# m2.net
KiCad netlist of a schematic drawn in EAGLE
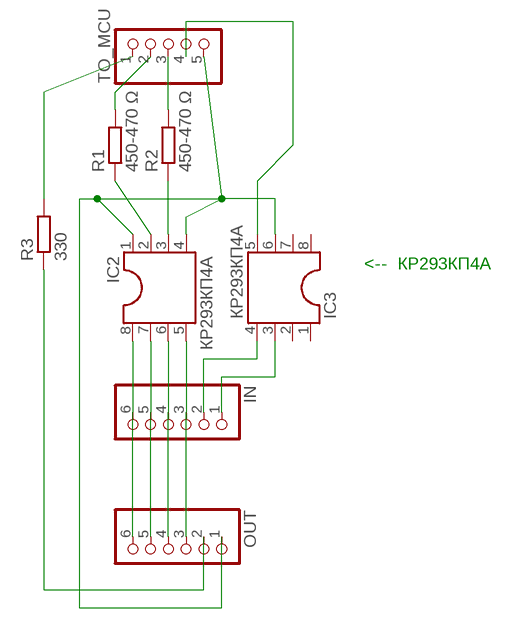
[diagram p0: schematic, sheet 1]

(export (version "E")
  (design (tool "Eeschema 10.0.6"))
  (components
    (comp (ref "IC2")
      (value "КР293КП4А")
      (footprint "eagle-import:DIL08")
      (libsource (lib "eagle-import") (part "DIL8"))
    )
    (comp (ref "IC3")
      (value "КР293КП4А")
      (footprint "eagle-import:DIL08")
      (libsource (lib "eagle-import") (part "DIL8"))
    )
    (comp (ref "IN")
      (value "PINHD-1X6")
      (footprint "eagle-import:1X06")
      (libsource (lib "eagle-import") (part "PINHD-1X6"))
    )
    (comp (ref "OUT")
      (value "PINHD-1X6")
      (footprint "eagle-import:1X06")
      (libsource (lib "eagle-import") (part "PINHD-1X6"))
    )
    (comp (ref "R1")
      (value "450-470 Ω")
      (footprint "eagle-import:0204_5")
      (libsource (lib "eagle-import") (part "R-EU_0204/5"))
    )
    (comp (ref "R2")
      (value "450-470 Ω")
      (footprint "eagle-import:0204_5")
      (libsource (lib "eagle-import") (part "R-EU_0204/5"))
    )
    (comp (ref "R3")
      (value "330")
      (footprint "eagle-import:0204_5")
      (libsource (lib "eagle-import") (part "R-EU_0204/5"))
    )
    (comp (ref "TO_MCU")
      (value "PINHD-1X5")
      (footprint "eagle-import:1X05")
      (libsource (lib "eagle-import") (part "PINHD-1X5"))
    )
  )
  (nets
    (net (code "1") (name "Net-(IC2-Pad1)") (class "Default")
      (node (ref "IC2") (pin "1") (pinfunction "1_1") (pintype "passive"))
      (node (ref "IC2") (pin "4") (pinfunction "4_4") (pintype "passive"))
      (node (ref "IC3") (pin "6") (pinfunction "6_6") (pintype "passive"))
      (node (ref "OUT") (pin "1") (pinfunction "1_1") (pintype "passive"))
      (node (ref "TO_MCU") (pin "5") (pinfunction "5_5") (pintype "passive"))
    )
    (net (code "2") (name "Net-(IC2-Pad2)") (class "Default")
      (node (ref "IC2") (pin "2") (pinfunction "2_2") (pintype "passive"))
      (node (ref "R1") (pin "1") (pinfunction "1_1") (pintype "passive"))
    )
    (net (code "3") (name "Net-(IC2-Pad3)") (class "Default")
      (node (ref "IC2") (pin "3") (pinfunction "3_3") (pintype "passive"))
      (node (ref "R2") (pin "1") (pinfunction "1_1") (pintype "passive"))
    )
    (net (code "4") (name "Net-(IC2-Pad5)") (class "Default")
      (node (ref "IC2") (pin "5") (pinfunction "5_5") (pintype "passive"))
      (node (ref "IN") (pin "3") (pinfunction "3_3") (pintype "passive"))
      (node (ref "OUT") (pin "3") (pinfunction "3_3") (pintype "passive"))
    )
    (net (code "5") (name "Net-(IC2-Pad6)") (class "Default")
      (node (ref "IC2") (pin "6") (pinfunction "6_6") (pintype "passive"))
      (node (ref "IN") (pin "4") (pinfunction "4_4") (pintype "passive"))
      (node (ref "OUT") (pin "4") (pinfunction "4_4") (pintype "passive"))
    )
    (net (code "6") (name "Net-(IC2-Pad7)") (class "Default")
      (node (ref "IC2") (pin "7") (pinfunction "7_7") (pintype "passive"))
      (node (ref "IN") (pin "5") (pinfunction "5_5") (pintype "passive"))
      (node (ref "OUT") (pin "5") (pinfunction "5_5") (pintype "passive"))
    )
    (net (code "7") (name "Net-(IC2-Pad8)") (class "Default")
      (node (ref "IC2") (pin "8") (pinfunction "8_8") (pintype "passive"))
      (node (ref "IN") (pin "6") (pinfunction "6_6") (pintype "passive"))
      (node (ref "OUT") (pin "6") (pinfunction "6_6") (pintype "passive"))
    )
    (net (code "8") (name "Net-(IC3-Pad3)") (class "Default")
      (node (ref "IC3") (pin "3") (pinfunction "3_3") (pintype "passive"))
      (node (ref "IN") (pin "1") (pinfunction "1_1") (pintype "passive"))
    )
    (net (code "9") (name "Net-(IC3-Pad4)") (class "Default")
      (node (ref "IC3") (pin "4") (pinfunction "4_4") (pintype "passive"))
      (node (ref "IN") (pin "2") (pinfunction "2_2") (pintype "passive"))
    )
    (net (code "10") (name "Net-(IC3-Pad5)") (class "Default")
      (node (ref "IC3") (pin "5") (pinfunction "5_5") (pintype "passive"))
      (node (ref "TO_MCU") (pin "4") (pinfunction "4_4") (pintype "passive"))
    )
    (net (code "11") (name "Net-(OUT-Pad2)") (class "Default")
      (node (ref "OUT") (pin "2") (pinfunction "2_2") (pintype "passive"))
      (node (ref "R3") (pin "1") (pinfunction "1_1") (pintype "passive"))
    )
    (net (code "12") (name "Net-(R1-Pad2)") (class "Default")
      (node (ref "R1") (pin "2") (pinfunction "2_2") (pintype "passive"))
      (node (ref "TO_MCU") (pin "2") (pinfunction "2_2") (pintype "passive"))
    )
    (net (code "13") (name "Net-(R2-Pad2)") (class "Default")
      (node (ref "R2") (pin "2") (pinfunction "2_2") (pintype "passive"))
      (node (ref "TO_MCU") (pin "3") (pinfunction "3_3") (pintype "passive"))
    )
    (net (code "14") (name "Net-(R3-Pad2)") (class "Default")
      (node (ref "R3") (pin "2") (pinfunction "2_2") (pintype "passive"))
      (node (ref "TO_MCU") (pin "1") (pinfunction "1_1") (pintype "passive"))
    )
    (net (code "15") (name "unconnected-(IC3-Pad1)") (class "Default")
      (node (ref "IC3") (pin "1") (pinfunction "1_1") (pintype "passive"))
    )
    (net (code "16") (name "unconnected-(IC3-Pad2)") (class "Default")
      (node (ref "IC3") (pin "2") (pinfunction "2_2") (pintype "passive"))
    )
    (net (code "17") (name "unconnected-(IC3-Pad7)") (class "Default")
      (node (ref "IC3") (pin "7") (pinfunction "7_7") (pintype "passive"))
    )
    (net (code "18") (name "unconnected-(IC3-Pad8)") (class "Default")
      (node (ref "IC3") (pin "8") (pinfunction "8_8") (pintype "passive"))
    )
  )
)
